# MAGI_sCore.net
KiCad netlist of a schematic drawn in Altium Designer
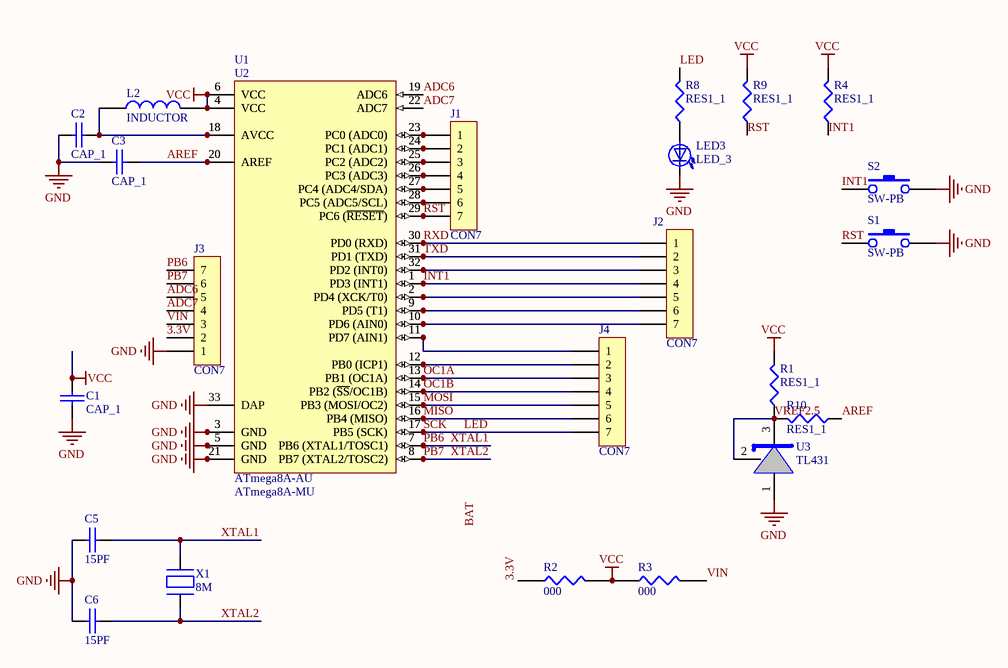
[diagram p0: MAGI'sCore.SchDoc]

(export (version "E")
  (design (tool "Eeschema 10.0.6"))
  (components
    (comp (ref "C1")
      (value "CAP_1")
      (footprint "1210")
      (description "Capacitor")
      (libsource (lib "电容器") (part "CAP_1"))
    )
    (comp (ref "C2")
      (value "CAP_1")
      (footprint "6-0805_N")
      (description "Capacitor")
      (libsource (lib "电容器") (part "CAP_1"))
    )
    (comp (ref "C3")
      (value "CAP_1")
      (footprint "6-0805_N")
      (description "Capacitor")
      (libsource (lib "电容器") (part "CAP_1"))
    )
    (comp (ref "C5") (value "15PF") (footprint "6-0805_n") (libsource (lib "STM32") (part "CAP")))
    (comp (ref "C6") (value "15PF") (footprint "6-0805_n") (libsource (lib "STM32") (part "CAP")))
    (comp (ref "J1")
      (value "CON7")
      (footprint "CON7")
      (description "Connector")
      (libsource (lib "") (part "CON7_1"))
    )
    (comp (ref "J2")
      (value "CON7")
      (footprint "CON7")
      (description "Connector")
      (libsource (lib "") (part "CON7_1"))
    )
    (comp (ref "J3")
      (value "CON7")
      (footprint "CON7")
      (description "Connector")
      (libsource (lib "CON系列") (part "CON7"))
    )
    (comp (ref "J4")
      (value "CON7")
      (footprint "CON7")
      (description "Connector")
      (libsource (lib "") (part "CON7_1"))
    )
    (comp (ref "L2") (value "INDUCTOR") (footprint "14-1210") (libsource (lib "汇总") (part "INDUCTOR")))
    (comp (ref "LED3") (value "LED_3") (footprint "6-0805_N") (libsource (lib "二极管") (part "LED_3")))
    (comp (ref "R1") (value "RES1_1") (footprint "6-0805_N") (libsource (lib "电阻器") (part "RES1_1")))
    (comp (ref "R2") (value "000") (footprint "6-0805_n") (libsource (lib "电阻器") (part "RES1")))
    (comp (ref "R3") (value "000") (footprint "6-0805_n") (libsource (lib "电阻器") (part "RES1")))
    (comp (ref "R4") (value "RES1_1") (footprint "6-0805_N") (libsource (lib "电阻器") (part "RES1_1")))
    (comp (ref "R8") (value "RES1_1") (footprint "6-0805_N") (libsource (lib "电阻器") (part "RES1_1")))
    (comp (ref "R9") (value "RES1_1") (footprint "6-0805_N") (libsource (lib "电阻器") (part "RES1_1")))
    (comp (ref "R10") (value "RES1_1") (footprint "6-0805_N") (libsource (lib "电阻器") (part "RES1_1")))
    (comp (ref "S1") (value "SW-PB") (footprint "SKRELGE010") (libsource (lib "手动开关") (part "SW-PB")))
    (comp (ref "S2") (value "SW-PB") (footprint "SKRELGE010") (libsource (lib "手动开关") (part "SW-PB")))
    (comp (ref "U1")
      (value "ATmega8A-AU")
      (footprint "32A_N")
      (fields (field (name "PUBLISHER") "Altium Limited"))
      (libsource (lib "Atmel Microcontroller 8-Bit megaAVR") (part "ATmega8A-AU"))
    )
    (comp (ref "U2")
      (value "ATmega8A-MU")
      (footprint "32M1-A_N")
      (fields (field (name "PUBLISHER") "Altium Limited"))
      (libsource (lib "Atmel Microcontroller 8-Bit megaAVR") (part "ATmega8A-MU"))
    )
    (comp (ref "U3") (value "TL431") (footprint "SOT23_N") (libsource (lib "汇总") (part "TL431")))
    (comp (ref "X1") (value "8M") (footprint "5032") (libsource (lib "STM32") (part "CRYSTAL")))
  )
  (nets
    (net (code "1") (name "/3.3V") (class "Default")
      (node (ref "J3") (pin "2") (pinfunction "2_2") (pintype "passive"))
      (node (ref "R2") (pin "1") (pinfunction "1_1") (pintype "passive"))
    )
    (net (code "2") (name "/ADC6") (class "Default")
      (node (ref "J3") (pin "5") (pinfunction "5_5") (pintype "passive"))
      (node (ref "U1") (pin "19") (pinfunction "ADC6_19") (pintype "input"))
      (node (ref "U2") (pin "19") (pinfunction "ADC6_19") (pintype "input"))
    )
    (net (code "3") (name "/ADC7") (class "Default")
      (node (ref "J3") (pin "4") (pinfunction "4_4") (pintype "passive"))
      (node (ref "U1") (pin "22") (pinfunction "ADC7_22") (pintype "input"))
      (node (ref "U2") (pin "22") (pinfunction "ADC7_22") (pintype "input"))
    )
    (net (code "4") (name "/AREF") (class "Default")
      (node (ref "C3") (pin "2") (pinfunction "2_2") (pintype "passive"))
      (node (ref "R10") (pin "1") (pinfunction "1_1") (pintype "passive"))
      (node (ref "U1") (pin "20") (pinfunction "AREF_20") (pintype "power_in"))
      (node (ref "U2") (pin "20") (pinfunction "AREF_20") (pintype "power_in"))
    )
    (net (code "6") (name "/INT1") (class "Default")
      (node (ref "J2") (pin "4") (pinfunction "4_4") (pintype "passive"))
      (node (ref "R4") (pin "1") (pinfunction "1_1") (pintype "passive"))
      (node (ref "S2") (pin "1") (pinfunction "1_1") (pintype "passive"))
      (node (ref "U1") (pin "1") (pinfunction "PD3_(INT1)_1") (pintype "bidirectional"))
      (node (ref "U2") (pin "1") (pinfunction "PD3_(INT1)_1") (pintype "bidirectional"))
    )
    (net (code "7") (name "/LED") (class "Default")
      (node (ref "J4") (pin "7") (pinfunction "7_7") (pintype "passive"))
      (node (ref "R8") (pin "2") (pinfunction "2_2") (pintype "passive"))
      (node (ref "U1") (pin "17") (pinfunction "PB5_(SCK)_17") (pintype "bidirectional"))
      (node (ref "U2") (pin "17") (pinfunction "PB5_(SCK)_17") (pintype "bidirectional"))
    )
    (net (code "8") (name "/MISO") (class "Default")
      (node (ref "J4") (pin "6") (pinfunction "6_6") (pintype "passive"))
      (node (ref "U1") (pin "16") (pinfunction "PB4_(MISO)_16") (pintype "bidirectional"))
      (node (ref "U2") (pin "16") (pinfunction "PB4_(MISO)_16") (pintype "bidirectional"))
    )
    (net (code "9") (name "/MOSI") (class "Default")
      (node (ref "J4") (pin "5") (pinfunction "5_5") (pintype "passive"))
      (node (ref "U1") (pin "15") (pinfunction "PB3_(MOSI/OC2)_15") (pintype "bidirectional"))
      (node (ref "U2") (pin "15") (pinfunction "PB3_(MOSI/OC2)_15") (pintype "bidirectional"))
    )
    (net (code "10") (name "/OC1A") (class "Default")
      (node (ref "J4") (pin "3") (pinfunction "3_3") (pintype "passive"))
      (node (ref "U1") (pin "13") (pinfunction "PB1_(OC1A)_13") (pintype "bidirectional"))
      (node (ref "U2") (pin "13") (pinfunction "PB1_(OC1A)_13") (pintype "bidirectional"))
    )
    (net (code "11") (name "/OC1B") (class "Default")
      (node (ref "J4") (pin "4") (pinfunction "4_4") (pintype "passive"))
      (node (ref "U1") (pin "14") (pinfunction "PB2_(~{SS}/OC1B)_14") (pintype "bidirectional"))
      (node (ref "U2") (pin "14") (pinfunction "PB2_(~{SS}/OC1B)_14") (pintype "bidirectional"))
    )
    (net (code "12") (name "/PB6") (class "Default")
      (node (ref "C5") (pin "2") (pinfunction "2_2") (pintype "passive"))
      (node (ref "J3") (pin "7") (pinfunction "7_7") (pintype "passive"))
      (node (ref "U1") (pin "7") (pinfunction "PB6_(XTAL1/TOSC1)_7") (pintype "bidirectional"))
      (node (ref "U2") (pin "7") (pinfunction "PB6_(XTAL1/TOSC1)_7") (pintype "bidirectional"))
      (node (ref "X1") (pin "1") (pinfunction "1_1") (pintype "passive"))
    )
    (net (code "13") (name "/PB7") (class "Default")
      (node (ref "C6") (pin "2") (pinfunction "2_2") (pintype "passive"))
      (node (ref "J3") (pin "6") (pinfunction "6_6") (pintype "passive"))
      (node (ref "U1") (pin "8") (pinfunction "PB7_(XTAL2/TOSC2)_8") (pintype "bidirectional"))
      (node (ref "U2") (pin "8") (pinfunction "PB7_(XTAL2/TOSC2)_8") (pintype "bidirectional"))
      (node (ref "X1") (pin "2") (pinfunction "2_2") (pintype "passive"))
    )
    (net (code "14") (name "/RST") (class "Default")
      (node (ref "J1") (pin "7") (pinfunction "7_7") (pintype "passive"))
      (node (ref "R9") (pin "1") (pinfunction "1_1") (pintype "passive"))
      (node (ref "S1") (pin "1") (pinfunction "1_1") (pintype "passive"))
      (node (ref "U1") (pin "29") (pinfunction "PC6_(~{RESET})_29") (pintype "bidirectional"))
      (node (ref "U2") (pin "29") (pinfunction "PC6_(~{RESET})_29") (pintype "bidirectional"))
    )
    (net (code "15") (name "/RXD") (class "Default")
      (node (ref "J2") (pin "1") (pinfunction "1_1") (pintype "passive"))
      (node (ref "U1") (pin "30") (pinfunction "PD0_(RXD)_30") (pintype "bidirectional"))
      (node (ref "U2") (pin "30") (pinfunction "PD0_(RXD)_30") (pintype "bidirectional"))
    )
    (net (code "16") (name "/TXD") (class "Default")
      (node (ref "J2") (pin "2") (pinfunction "2_2") (pintype "passive"))
      (node (ref "U1") (pin "31") (pinfunction "PD1_(TXD)_31") (pintype "bidirectional"))
      (node (ref "U2") (pin "31") (pinfunction "PD1_(TXD)_31") (pintype "bidirectional"))
    )
    (net (code "17") (name "/VIN") (class "Default")
      (node (ref "J3") (pin "3") (pinfunction "3_3") (pintype "passive"))
      (node (ref "R3") (pin "2") (pinfunction "2_2") (pintype "passive"))
    )
    (net (code "18") (name "/VREF2.5") (class "Default")
      (node (ref "R1") (pin "1") (pinfunction "1_1") (pintype "passive"))
      (node (ref "R10") (pin "2") (pinfunction "2_2") (pintype "passive"))
      (node (ref "U3") (pin "2") (pinfunction "REF_2") (pintype "passive"))
      (node (ref "U3") (pin "3") (pinfunction "ANODE_3") (pintype "passive"))
    )
    (net (code "19") (name "GND") (class "Default")
      (node (ref "C1") (pin "1") (pinfunction "1_1") (pintype "passive"))
      (node (ref "C2") (pin "1") (pinfunction "1_1") (pintype "passive"))
      (node (ref "C3") (pin "1") (pinfunction "1_1") (pintype "passive"))
      (node (ref "C5") (pin "1") (pinfunction "1_1") (pintype "passive"))
      (node (ref "C6") (pin "1") (pinfunction "1_1") (pintype "passive"))
      (node (ref "J3") (pin "1") (pinfunction "1_1") (pintype "passive"))
      (node (ref "LED3") (pin "2") (pinfunction "K_2") (pintype "passive"))
      (node (ref "S1") (pin "2") (pinfunction "2_2") (pintype "passive"))
      (node (ref "S2") (pin "2") (pinfunction "2_2") (pintype "passive"))
      (node (ref "U1") (pin "21") (pinfunction "GND_21") (pintype "power_in"))
      (node (ref "U1") (pin "3") (pinfunction "GND_3") (pintype "power_in"))
      (node (ref "U1") (pin "5") (pinfunction "GND_5") (pintype "power_in"))
      (node (ref "U2") (pin "21") (pinfunction "GND_21") (pintype "power_in"))
      (node (ref "U2") (pin "3") (pinfunction "GND_3") (pintype "power_in"))
      (node (ref "U2") (pin "33") (pinfunction "DAP_33") (pintype "power_in"))
      (node (ref "U2") (pin "5") (pinfunction "GND_5") (pintype "power_in"))
      (node (ref "U3") (pin "1") (pinfunction "CATHODE_1") (pintype "passive"))
    )
    (net (code "20") (name "Net-(LED3-A)") (class "Default")
      (node (ref "LED3") (pin "1") (pinfunction "A_1") (pintype "passive"))
      (node (ref "R8") (pin "1") (pinfunction "1_1") (pintype "passive"))
    )
    (net (code "21") (name "Net-(U1-AVCC)") (class "Default")
      (node (ref "C2") (pin "2") (pinfunction "2_2") (pintype "passive"))
      (node (ref "L2") (pin "1") (pinfunction "1_1") (pintype "passive"))
      (node (ref "U1") (pin "18") (pinfunction "AVCC_18") (pintype "power_in"))
      (node (ref "U2") (pin "18") (pinfunction "AVCC_18") (pintype "power_in"))
    )
    (net (code "22") (name "Net-(U1-PB0_(ICP1))") (class "Default")
      (node (ref "J4") (pin "2") (pinfunction "2_2") (pintype "passive"))
      (node (ref "U1") (pin "12") (pinfunction "PB0_(ICP1)_12") (pintype "bidirectional"))
      (node (ref "U2") (pin "12") (pinfunction "PB0_(ICP1)_12") (pintype "bidirectional"))
    )
    (net (code "23") (name "Net-(U1-PC0_(ADC0))") (class "Default")
      (node (ref "J1") (pin "1") (pinfunction "1_1") (pintype "passive"))
      (node (ref "U1") (pin "23") (pinfunction "PC0_(ADC0)_23") (pintype "bidirectional"))
      (node (ref "U2") (pin "23") (pinfunction "PC0_(ADC0)_23") (pintype "bidirectional"))
    )
    (net (code "24") (name "Net-(U1-PC1_(ADC1))") (class "Default")
      (node (ref "J1") (pin "2") (pinfunction "2_2") (pintype "passive"))
      (node (ref "U1") (pin "24") (pinfunction "PC1_(ADC1)_24") (pintype "bidirectional"))
      (node (ref "U2") (pin "24") (pinfunction "PC1_(ADC1)_24") (pintype "bidirectional"))
    )
    (net (code "25") (name "Net-(U1-PC2_(ADC2))") (class "Default")
      (node (ref "J1") (pin "3") (pinfunction "3_3") (pintype "passive"))
      (node (ref "U1") (pin "25") (pinfunction "PC2_(ADC2)_25") (pintype "bidirectional"))
      (node (ref "U2") (pin "25") (pinfunction "PC2_(ADC2)_25") (pintype "bidirectional"))
    )
    (net (code "26") (name "Net-(U1-PC3_(ADC3))") (class "Default")
      (node (ref "J1") (pin "4") (pinfunction "4_4") (pintype "passive"))
      (node (ref "U1") (pin "26") (pinfunction "PC3_(ADC3)_26") (pintype "bidirectional"))
      (node (ref "U2") (pin "26") (pinfunction "PC3_(ADC3)_26") (pintype "bidirectional"))
    )
    (net (code "27") (name "Net-(U1-PC4_(ADC4{slash}SDA))") (class "Default")
      (node (ref "J1") (pin "5") (pinfunction "5_5") (pintype "passive"))
      (node (ref "U1") (pin "27") (pinfunction "PC4_(ADC4/SDA)_27") (pintype "bidirectional"))
      (node (ref "U2") (pin "27") (pinfunction "PC4_(ADC4/SDA)_27") (pintype "bidirectional"))
    )
    (net (code "28") (name "Net-(U1-PC5_(ADC5{slash}SCL))") (class "Default")
      (node (ref "J1") (pin "6") (pinfunction "6_6") (pintype "passive"))
      (node (ref "U1") (pin "28") (pinfunction "PC5_(ADC5/SCL)_28") (pintype "bidirectional"))
      (node (ref "U2") (pin "28") (pinfunction "PC5_(ADC5/SCL)_28") (pintype "bidirectional"))
    )
    (net (code "29") (name "Net-(U1-PD2_(INT0))") (class "Default")
      (node (ref "J2") (pin "3") (pinfunction "3_3") (pintype "passive"))
      (node (ref "U1") (pin "32") (pinfunction "PD2_(INT0)_32") (pintype "bidirectional"))
      (node (ref "U2") (pin "32") (pinfunction "PD2_(INT0)_32") (pintype "bidirectional"))
    )
    (net (code "30") (name "Net-(U1-PD4_(XCK{slash}T0))") (class "Default")
      (node (ref "J2") (pin "5") (pinfunction "5_5") (pintype "passive"))
      (node (ref "U1") (pin "2") (pinfunction "PD4_(XCK/T0)_2") (pintype "bidirectional"))
      (node (ref "U2") (pin "2") (pinfunction "PD4_(XCK/T0)_2") (pintype "bidirectional"))
    )
    (net (code "31") (name "Net-(U1-PD5_(T1))") (class "Default")
      (node (ref "J2") (pin "6") (pinfunction "6_6") (pintype "passive"))
      (node (ref "U1") (pin "9") (pinfunction "PD5_(T1)_9") (pintype "bidirectional"))
      (node (ref "U2") (pin "9") (pinfunction "PD5_(T1)_9") (pintype "bidirectional"))
    )
    (net (code "32") (name "Net-(U1-PD6_(AIN0))") (class "Default")
      (node (ref "J2") (pin "7") (pinfunction "7_7") (pintype "passive"))
      (node (ref "U1") (pin "10") (pinfunction "PD6_(AIN0)_10") (pintype "bidirectional"))
      (node (ref "U2") (pin "10") (pinfunction "PD6_(AIN0)_10") (pintype "bidirectional"))
    )
    (net (code "33") (name "Net-(U1-PD7_(AIN1))") (class "Default")
      (node (ref "J4") (pin "1") (pinfunction "1_1") (pintype "passive"))
      (node (ref "U1") (pin "11") (pinfunction "PD7_(AIN1)_11") (pintype "bidirectional"))
      (node (ref "U2") (pin "11") (pinfunction "PD7_(AIN1)_11") (pintype "bidirectional"))
    )
    (net (code "34") (name "VCC") (class "Default")
      (node (ref "C1") (pin "2") (pinfunction "2_2") (pintype "passive"))
      (node (ref "L2") (pin "2") (pinfunction "2_2") (pintype "passive"))
      (node (ref "R1") (pin "2") (pinfunction "2_2") (pintype "passive"))
      (node (ref "R2") (pin "2") (pinfunction "2_2") (pintype "passive"))
      (node (ref "R3") (pin "1") (pinfunction "1_1") (pintype "passive"))
      (node (ref "R4") (pin "2") (pinfunction "2_2") (pintype "passive"))
      (node (ref "R9") (pin "2") (pinfunction "2_2") (pintype "passive"))
      (node (ref "U1") (pin "4") (pinfunction "VCC_4") (pintype "power_in"))
      (node (ref "U1") (pin "6") (pinfunction "VCC_6") (pintype "power_in"))
      (node (ref "U2") (pin "4") (pinfunction "VCC_4") (pintype "power_in"))
      (node (ref "U2") (pin "6") (pinfunction "VCC_6") (pintype "power_in"))
    )
  )
)
